# Adafruit_DRV8833.net
KiCad netlist of a schematic drawn in Altium Designer
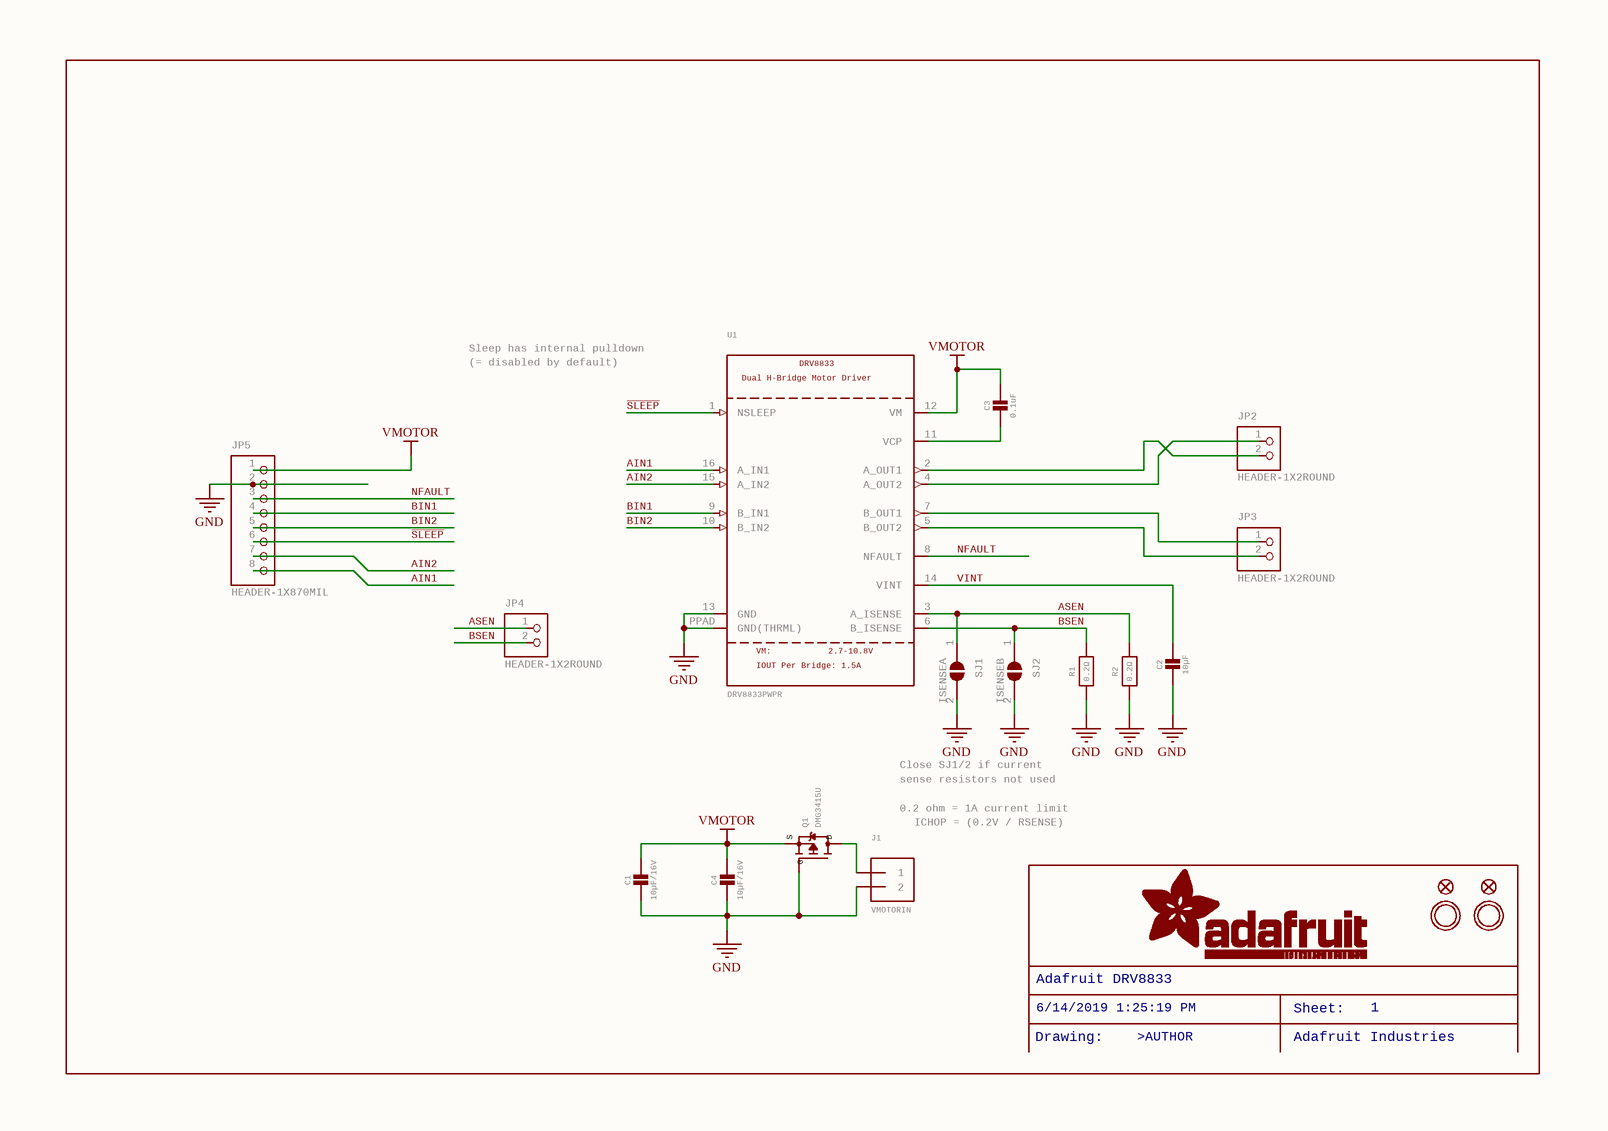
[diagram p0: Adafruit DRV8833.SchDoc]

(export (version "E")
  (design (tool "Eeschema 10.0.6"))
  (components
    (comp (ref "C1")
      (value "10µF/16V")
      (footprint "0805-NO")
      (libsource (lib "microbuilder") (part "CAP_CERAMIC0805-NOOUTLINE"))
    )
    (comp (ref "C2")
      (value "10µF")
      (footprint "0805-NO")
      (libsource (lib "microbuilder") (part "CAP_CERAMIC0805-NOOUTLINE"))
    )
    (comp (ref "C3")
      (value "0.1uF")
      (footprint "0805-NO")
      (libsource (lib "microbuilder") (part "CAP_CERAMIC0805-NOOUTLINE"))
    )
    (comp (ref "C4")
      (value "10µF/16V")
      (footprint "0805-NO")
      (libsource (lib "microbuilder") (part "CAP_CERAMIC0805-NOOUTLINE"))
    )
    (comp (ref "FID1")
      (value "FIDUCIAL\"\"")
      (footprint "FIDUCIAL_1MM")
      (description "Fiducial Alignment Points   Various fiducial points for machine vision alignment.")
      (libsource (lib "microbuilder") (part "FIDUCIAL{dblquote}{dblquote}"))
    )
    (comp (ref "FID2")
      (value "FIDUCIAL\"\"")
      (footprint "FIDUCIAL_1MM")
      (description "Fiducial Alignment Points   Various fiducial points for machine vision alignment.")
      (libsource (lib "microbuilder") (part "FIDUCIAL{dblquote}{dblquote}"))
    )
    (comp (ref "J1")
      (value "VMOTORIN")
      (footprint "TERMBLOCK_1X2-3.5MM")
      (description "3.5mm Terminal block    http://www.ladyada.net/library/pcb/eaglelibrary.html")
      (libsource (lib "microbuilder") (part "TERMBLOCK_1X2"))
    )
    (comp (ref "JP2")
      (value "HEADER-1X2ROUND")
      (footprint "1X02_ROUND")
      (description "PIN HEADER")
      (libsource (lib "microbuilder") (part "HEADER-1X2ROUND"))
    )
    (comp (ref "JP3")
      (value "HEADER-1X2ROUND")
      (footprint "1X02_ROUND")
      (description "PIN HEADER")
      (libsource (lib "microbuilder") (part "HEADER-1X2ROUND"))
    )
    (comp (ref "JP4")
      (value "HEADER-1X2ROUND")
      (footprint "1X02_ROUND")
      (description "PIN HEADER")
      (libsource (lib "microbuilder") (part "HEADER-1X2ROUND"))
    )
    (comp (ref "JP5")
      (value "HEADER-1X870MIL")
      (footprint "1X08_ROUND_70")
      (description "PIN HEADER")
      (libsource (lib "microbuilder") (part "HEADER-1X870MIL"))
    )
    (comp (ref "Q1")
      (value "DMG3415U")
      (footprint "SOT23-WIDE")
      (fields (field (name "D") "D") (field (name "S") "S") (field (name "G") "G"))
      (libsource (lib "microbuilder") (part "MOSFET-PWIDE"))
    )
    (comp (ref "R1")
      (value "0.2Ω")
      (footprint "_1206")
      (libsource (lib "microbuilder") (part "RESISTOR_1206"))
    )
    (comp (ref "R2")
      (value "0.2Ω")
      (footprint "_1206")
      (libsource (lib "microbuilder") (part "RESISTOR_1206"))
    )
    (comp (ref "SJ1")
      (value "ISENSEA")
      (footprint "SOLDERJUMPER_ARROW_NOPASTE")
      (libsource (lib "microbuilder") (part "SOLDERJUMPER"))
    )
    (comp (ref "SJ2")
      (value "ISENSEB")
      (footprint "SOLDERJUMPER_ARROW_NOPASTE")
      (libsource (lib "microbuilder") (part "SOLDERJUMPER"))
    )
    (comp (ref "U$13")
      (value "MOUNTINGHOLE2.5")
      (footprint "MOUNTINGHOLE_2.5_PLATED")
      (description "Mounting Hole   For #2 screws (0.086\"/2.18mm width, 0.094\"/2.4mm hole) use 2.5mm")
      (libsource (lib "microbuilder") (part "MOUNTINGHOLE2.5"))
    )
    (comp (ref "U$14")
      (value "MOUNTINGHOLE2.5")
      (footprint "MOUNTINGHOLE_2.5_PLATED")
      (description "Mounting Hole   For #2 screws (0.086\"/2.18mm width, 0.094\"/2.4mm hole) use 2.5mm")
      (libsource (lib "microbuilder") (part "MOUNTINGHOLE2.5"))
    )
    (comp (ref "U1")
      (value "DRV8833PWPR")
      (footprint "HTSSOP16")
      (description "DRV8833 Dual H-Bridge Motor Driver -- HTSSOP Package")
      (fields
        (field (name "DRV8833") "DRV8833")
        (field (name "DUALH-BRIDGEMOTORDRIVER") "Dual H-Bridge Motor Driver")
        (field (name "VM") "VM:")
        (field (name "2.7-10.8V") "2.7-10.8V")
        (field (name "IOUTPERBRIDGE:1.5A") "IOUT Per Bridge: 1.5A")
      )
      (libsource (lib "microbuilder") (part "DRV8833"))
    )
  )
  (nets
    (net (code "1") (name "/AIN1") (class "Default")
      (node (ref "JP5") (pin "8") (pinfunction "8_8") (pintype "passive"))
      (node (ref "U1") (pin "16") (pinfunction "A_IN1_16") (pintype "input"))
    )
    (net (code "2") (name "/AIN2") (class "Default")
      (node (ref "JP5") (pin "7") (pinfunction "7_7") (pintype "passive"))
      (node (ref "U1") (pin "15") (pinfunction "A_IN2_15") (pintype "input"))
    )
    (net (code "3") (name "/ASEN") (class "Default")
      (node (ref "JP4") (pin "1") (pinfunction "1_1") (pintype "passive"))
      (node (ref "R2") (pin "2") (pinfunction "2_2") (pintype "passive"))
      (node (ref "SJ1") (pin "1") (pinfunction "1_1") (pintype "passive"))
      (node (ref "U1") (pin "3") (pinfunction "A_ISENSE_3") (pintype "bidirectional"))
    )
    (net (code "4") (name "/BIN1") (class "Default")
      (node (ref "JP5") (pin "4") (pinfunction "4_4") (pintype "passive"))
      (node (ref "U1") (pin "9") (pinfunction "B_IN1_9") (pintype "input"))
    )
    (net (code "5") (name "/BIN2") (class "Default")
      (node (ref "JP5") (pin "5") (pinfunction "5_5") (pintype "passive"))
      (node (ref "U1") (pin "10") (pinfunction "B_IN2_10") (pintype "input"))
    )
    (net (code "6") (name "/BSEN") (class "Default")
      (node (ref "JP4") (pin "2") (pinfunction "2_2") (pintype "passive"))
      (node (ref "R1") (pin "2") (pinfunction "2_2") (pintype "passive"))
      (node (ref "SJ2") (pin "1") (pinfunction "1_1") (pintype "passive"))
      (node (ref "U1") (pin "6") (pinfunction "B_ISENSE_6") (pintype "bidirectional"))
    )
    (net (code "7") (name "/NFAULT") (class "Default")
      (node (ref "JP5") (pin "3") (pinfunction "3_3") (pintype "passive"))
      (node (ref "U1") (pin "8") (pinfunction "NFAULT_8") (pintype "bidirectional"))
    )
    (net (code "8") (name "/VINT") (class "Default")
      (node (ref "C2") (pin "1") (pinfunction "1_1") (pintype "passive"))
      (node (ref "U1") (pin "14") (pinfunction "VINT_14") (pintype "power_in"))
    )
    (net (code "9") (name "/~{SLEEP}") (class "Default")
      (node (ref "JP5") (pin "6") (pinfunction "6_6") (pintype "passive"))
      (node (ref "U1") (pin "1") (pinfunction "NSLEEP_1") (pintype "input"))
    )
    (net (code "10") (name "GND") (class "Default")
      (node (ref "C1") (pin "2") (pinfunction "2_2") (pintype "passive"))
      (node (ref "C2") (pin "2") (pinfunction "2_2") (pintype "passive"))
      (node (ref "C4") (pin "2") (pinfunction "2_2") (pintype "passive"))
      (node (ref "J1") (pin "2") (pinfunction "2_2") (pintype "passive"))
      (node (ref "JP5") (pin "2") (pinfunction "2_2") (pintype "passive"))
      (node (ref "Q1") (pin "1") (pinfunction "G_1") (pintype "passive"))
      (node (ref "R1") (pin "1") (pinfunction "1_1") (pintype "passive"))
      (node (ref "R2") (pin "1") (pinfunction "1_1") (pintype "passive"))
      (node (ref "SJ1") (pin "2") (pinfunction "2_2") (pintype "passive"))
      (node (ref "SJ2") (pin "2") (pinfunction "2_2") (pintype "passive"))
      (node (ref "U1") (pin "13") (pinfunction "GND_13") (pintype "power_in"))
      (node (ref "U1") (pin "PPAD") (pinfunction "GND(THRML)_PPAD") (pintype "power_in"))
    )
    (net (code "11") (name "Net-(Q1-D)") (class "Default")
      (node (ref "J1") (pin "1") (pinfunction "1_1") (pintype "passive"))
      (node (ref "Q1") (pin "3") (pinfunction "D_3") (pintype "passive"))
    )
    (net (code "12") (name "Net-(U1-A_OUT1)") (class "Default")
      (node (ref "JP2") (pin "2") (pinfunction "2_2") (pintype "passive"))
      (node (ref "U1") (pin "2") (pinfunction "A_OUT1_2") (pintype "output"))
    )
    (net (code "13") (name "Net-(U1-A_OUT2)") (class "Default")
      (node (ref "JP2") (pin "1") (pinfunction "1_1") (pintype "passive"))
      (node (ref "U1") (pin "4") (pinfunction "A_OUT2_4") (pintype "output"))
    )
    (net (code "14") (name "Net-(U1-B_OUT1)") (class "Default")
      (node (ref "JP3") (pin "1") (pinfunction "1_1") (pintype "passive"))
      (node (ref "U1") (pin "7") (pinfunction "B_OUT1_7") (pintype "output"))
    )
    (net (code "15") (name "Net-(U1-B_OUT2)") (class "Default")
      (node (ref "JP3") (pin "2") (pinfunction "2_2") (pintype "passive"))
      (node (ref "U1") (pin "5") (pinfunction "B_OUT2_5") (pintype "output"))
    )
    (net (code "16") (name "Net-(U1-VCP)") (class "Default")
      (node (ref "C3") (pin "2") (pinfunction "2_2") (pintype "passive"))
      (node (ref "U1") (pin "11") (pinfunction "VCP_11") (pintype "bidirectional"))
    )
    (net (code "17") (name "VMOTOR") (class "Default")
      (node (ref "C1") (pin "1") (pinfunction "1_1") (pintype "passive"))
      (node (ref "C3") (pin "1") (pinfunction "1_1") (pintype "passive"))
      (node (ref "C4") (pin "1") (pinfunction "1_1") (pintype "passive"))
      (node (ref "JP5") (pin "1") (pinfunction "1_1") (pintype "passive"))
      (node (ref "Q1") (pin "2") (pinfunction "S_2") (pintype "passive"))
      (node (ref "U1") (pin "12") (pinfunction "VM_12") (pintype "power_in"))
    )
  )
)
